# Main_Schematic.net
KiCad netlist of a schematic drawn in Altium Designer
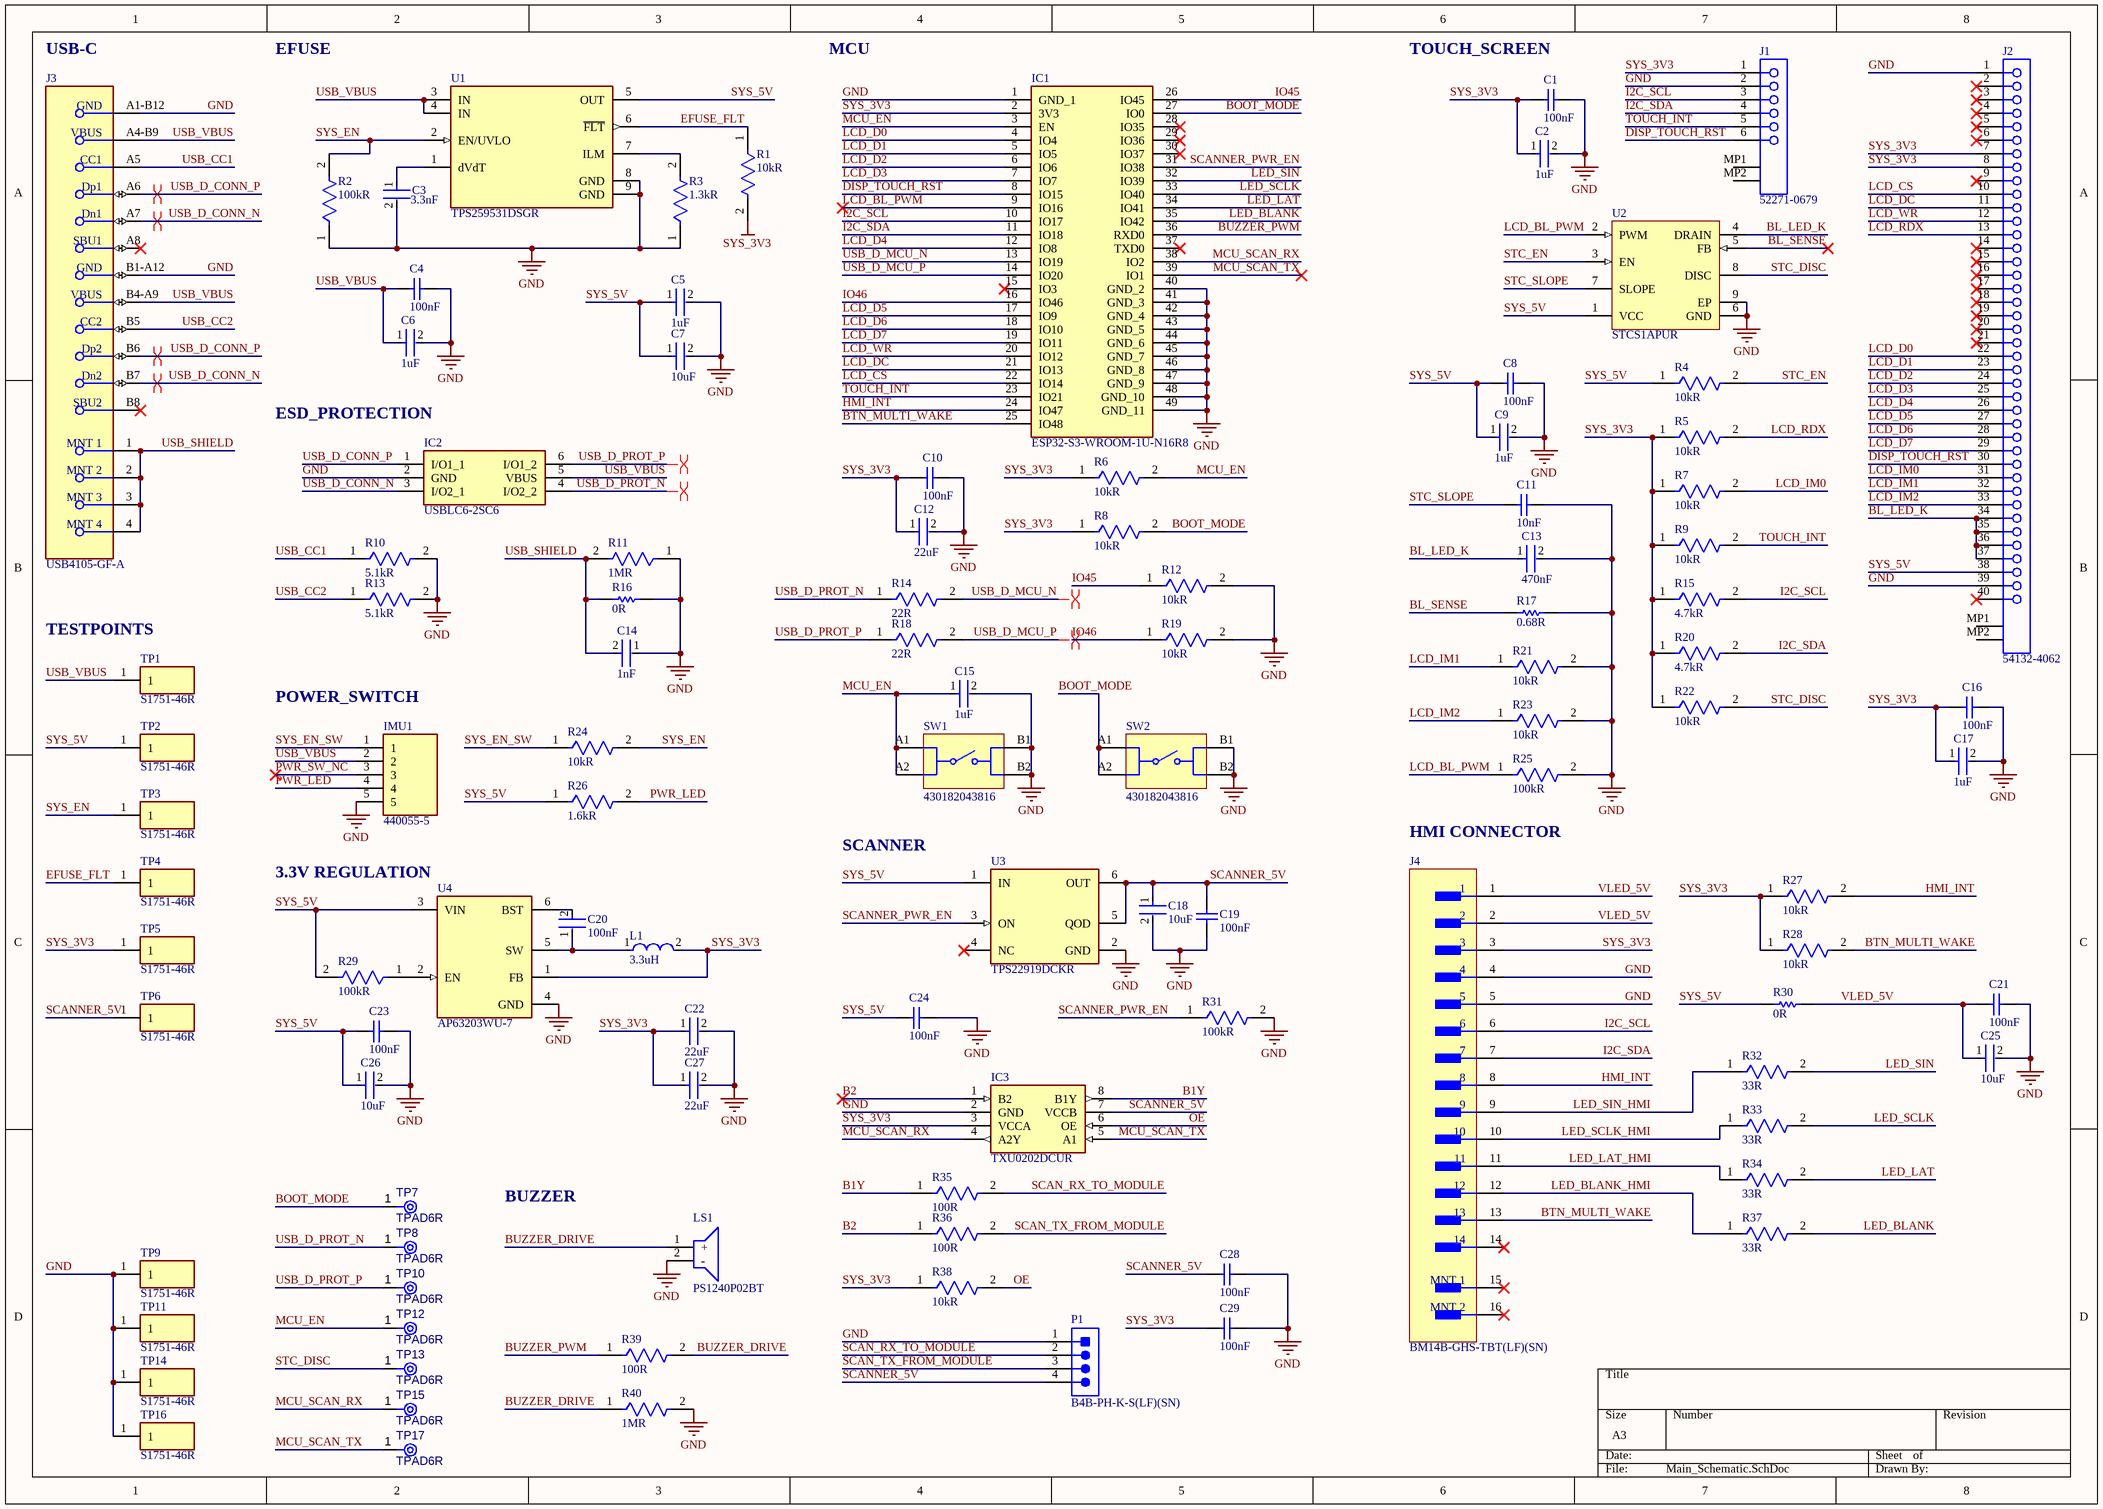
[diagram p0: Main_Schematic.SchDoc]

(export (version "E")
  (design (tool "Eeschema 10.0.6"))
  (components
    (comp (ref "C1")
      (value "100nF")
      (footprint "CAPC1608X90X35ML10T15")
      (description "Chip Capacitor, 100 nF, +/- 10%, 50 V, -55 to 125 degC, 0603 (1608 Metric), RoHS, Tape and Reel")
      (fields (field (name "MANUFACTURER") "Murata"))
      (libsource (lib "Altium Content Vault") (part "CAP-NP-2"))
    )
    (comp (ref "C2")
      (value "1uF")
      (footprint "FP-GRT188-0_1-e0_2_0_5-IPC_C")
      (description "Multi-Layer Ceramic Capacitor 1uF 25V X7R ±10% 0603 Paper T/R")
      (libsource (lib "Altium Content Vault") (part "02cd4be3c70576c341d710602a673aa"))
    )
    (comp (ref "C3")
      (value "3.3nF")
      (footprint "FP-GCM188-0_1-IPC_A")
      (description "Ceramic Capacitor for Automotive 3.3nF  ±5% 50VDC C0G 0603 Paper T/R")
      (fields (field (name "TOLERANCE") "5%"))
      (libsource (lib "Altium Content Vault") (part "02cd4be3c70576c341d710602a673aa"))
    )
    (comp (ref "C4")
      (value "100nF")
      (footprint "CAPC1608X90X35ML10T15")
      (description "Chip Capacitor, 100 nF, +/- 10%, 50 V, -55 to 125 degC, 0603 (1608 Metric), RoHS, Tape and Reel")
      (fields (field (name "MANUFACTURER") "Murata"))
      (libsource (lib "Altium Content Vault") (part "CAP-NP-2"))
    )
    (comp (ref "C5")
      (value "1uF")
      (footprint "FP-GRT188-0_1-e0_2_0_5-IPC_C")
      (description "Multi-Layer Ceramic Capacitor 1uF 25V X7R ±10% 0603 Paper T/R")
      (libsource (lib "Altium Content Vault") (part "02cd4be3c70576c341d710602a673aa"))
    )
    (comp (ref "C6")
      (value "1uF")
      (footprint "FP-GRT188-0_1-e0_2_0_5-IPC_C")
      (description "Multi-Layer Ceramic Capacitor 1uF 25V X7R ±10% 0603 Paper T/R")
      (libsource (lib "Altium Content Vault") (part "02cd4be3c70576c341d710602a673aa"))
    )
    (comp (ref "C7")
      (value "10uF")
      (footprint "FP-GRM21B-0_15-IPC_A")
      (description "Chip Multilayer Ceramic Capacitors for General Purpose, 0805, 10uF, X5R, 15%, 20%, 25V")
      (fields (field (name "TOLERANCE") "20%"))
      (libsource (lib "Altium Content Vault") (part "b4654b650e69147ec39a6b967a45e02"))
    )
    (comp (ref "C8")
      (value "100nF")
      (footprint "CAPC1608X90X35ML10T15")
      (description "Chip Capacitor, 100 nF, +/- 10%, 50 V, -55 to 125 degC, 0603 (1608 Metric), RoHS, Tape and Reel")
      (fields (field (name "MANUFACTURER") "Murata"))
      (libsource (lib "Altium Content Vault") (part "CAP-NP-2"))
    )
    (comp (ref "C9")
      (value "1uF")
      (footprint "FP-GRT188-0_1-e0_2_0_5-IPC_C")
      (description "Multi-Layer Ceramic Capacitor 1uF 25V X7R ±10% 0603 Paper T/R")
      (libsource (lib "Altium Content Vault") (part "02cd4be3c70576c341d710602a673aa"))
    )
    (comp (ref "C10")
      (value "100nF")
      (footprint "CAPC1608X90X35ML10T15")
      (description "Chip Capacitor, 100 nF, +/- 10%, 50 V, -55 to 125 degC, 0603 (1608 Metric), RoHS, Tape and Reel")
      (fields (field (name "MANUFACTURER") "Murata"))
      (libsource (lib "Altium Content Vault") (part "CAP-NP-2"))
    )
    (comp (ref "C11")
      (value "10nF")
      (footprint "CAPC1608X87X35LL15T15")
      (fields (field (name "MANUFACTURER") "Kemet") (field (name "PART NUMBER") "C0603C103J5RALTU"))
      (libsource (lib "Altium Content Vault") (part "CAP"))
    )
    (comp (ref "C12")
      (value "22uF")
      (footprint "FP-GRM319-0_15-IPC_C")
      (description "Chip Multilayer Ceramic Capacitors for General Purpose, 1206, 22uF, X5R, 15%, 20%, 16V")
      (fields (field (name "TOLERANCE") "20%"))
      (libsource (lib "Altium Content Vault") (part "b4654b650e69147ec39a6b967a45e02"))
    )
    (comp (ref "C13")
      (value "470nF")
      (footprint "FP-C0603C-CF-MFG")
      (description "CAP CER SMD 0603 .47UF 5% X7R 16")
      (fields (field (name "TOLERANCE") "0.05") (field (name "MANUFACTURER") "KEMET"))
      (libsource (lib "Altium Content Vault") (part "b4654b650e69147ec39a6b967a45e02"))
    )
    (comp (ref "C14")
      (value "1nF")
      (footprint "FP-GCJ188-0_2-IPC_A")
      (description "Cap Ceramic 1000pF 50V X7R 10% Pad SMD 0603 Soft Termination +125°C Automotive T/R")
      (fields (field (name "TOLERANCE") "10%"))
      (libsource (lib "Altium Content Vault") (part "f23184f103b6ebe33a8c269c53dcba6"))
    )
    (comp (ref "C15")
      (value "1uF")
      (footprint "FP-GRT188-0_1-e0_2_0_5-IPC_C")
      (description "Multi-Layer Ceramic Capacitor 1uF 25V X7R ±10% 0603 Paper T/R")
      (libsource (lib "Altium Content Vault") (part "02cd4be3c70576c341d710602a673aa"))
    )
    (comp (ref "C16")
      (value "100nF")
      (footprint "CAPC1608X90X35ML10T15")
      (description "Chip Capacitor, 100 nF, +/- 10%, 50 V, -55 to 125 degC, 0603 (1608 Metric), RoHS, Tape and Reel")
      (fields (field (name "MANUFACTURER") "Murata"))
      (libsource (lib "Altium Content Vault") (part "CAP-NP-2"))
    )
    (comp (ref "C17")
      (value "1uF")
      (footprint "FP-GRT188-0_1-e0_2_0_5-IPC_C")
      (description "Multi-Layer Ceramic Capacitor 1uF 25V X7R ±10% 0603 Paper T/R")
      (libsource (lib "Altium Content Vault") (part "02cd4be3c70576c341d710602a673aa"))
    )
    (comp (ref "C18")
      (value "10uF")
      (footprint "FP-GRM21B-0_15-IPC_A")
      (description "Chip Multilayer Ceramic Capacitors for General Purpose, 0805, 10uF, X5R, 15%, 20%, 25V")
      (fields (field (name "TOLERANCE") "20%"))
      (libsource (lib "Altium Content Vault") (part "b4654b650e69147ec39a6b967a45e02"))
    )
    (comp (ref "C19")
      (value "100nF")
      (footprint "CAPC1608X90X35ML10T15")
      (description "Chip Capacitor, 100 nF, +/- 10%, 50 V, -55 to 125 degC, 0603 (1608 Metric), RoHS, Tape and Reel")
      (fields (field (name "MANUFACTURER") "Murata"))
      (libsource (lib "Altium Content Vault") (part "CAP-NP-2"))
    )
    (comp (ref "C20")
      (value "100nF")
      (footprint "FP-GCJ188-0_2-IPC_C")
      (description "Cap Ceramic 0.1uF 50V X7R 10% Pad SMD 0603 Soft Termination +125°C Automotive T/R")
      (fields (field (name "TOLERANCE") "10%"))
      (libsource (lib "Altium Content Vault") (part "f23184f103b6ebe33a8c269c53dcba6"))
    )
    (comp (ref "C21")
      (value "100nF")
      (footprint "CAPC1608X90X35ML10T15")
      (description "Chip Capacitor, 100 nF, +/- 10%, 50 V, -55 to 125 degC, 0603 (1608 Metric), RoHS, Tape and Reel")
      (fields (field (name "MANUFACTURER") "Murata"))
      (libsource (lib "Altium Content Vault") (part "CAP-NP-2"))
    )
    (comp (ref "C22")
      (value "22uF")
      (footprint "FP-GRM319-0_15-IPC_C")
      (description "Chip Multilayer Ceramic Capacitors for General Purpose, 1206, 22uF, X5R, 15%, 20%, 16V")
      (fields (field (name "TOLERANCE") "20%"))
      (libsource (lib "Altium Content Vault") (part "b4654b650e69147ec39a6b967a45e02"))
    )
    (comp (ref "C23")
      (value "100nF")
      (footprint "CAPC1608X90X35ML10T15")
      (description "Chip Capacitor, 100 nF, +/- 10%, 50 V, -55 to 125 degC, 0603 (1608 Metric), RoHS, Tape and Reel")
      (fields (field (name "MANUFACTURER") "Murata"))
      (libsource (lib "Altium Content Vault") (part "CAP-NP-2"))
    )
    (comp (ref "C24")
      (value "100nF")
      (footprint "CAPC1608X90X35ML10T15")
      (description "Chip Capacitor, 100 nF, +/- 10%, 50 V, -55 to 125 degC, 0603 (1608 Metric), RoHS, Tape and Reel")
      (fields (field (name "MANUFACTURER") "Murata"))
      (libsource (lib "Altium Content Vault") (part "CAP-NP-2"))
    )
    (comp (ref "C25")
      (value "10uF")
      (footprint "FP-GRM21B-0_15-IPC_A")
      (description "Chip Multilayer Ceramic Capacitors for General Purpose, 0805, 10uF, X5R, 15%, 20%, 25V")
      (fields (field (name "TOLERANCE") "20%"))
      (libsource (lib "Altium Content Vault") (part "b4654b650e69147ec39a6b967a45e02"))
    )
    (comp (ref "C26")
      (value "10uF")
      (footprint "FP-GRM21B-0_15-IPC_A")
      (description "Chip Multilayer Ceramic Capacitors for General Purpose, 0805, 10uF, X5R, 15%, 20%, 25V")
      (fields (field (name "TOLERANCE") "20%"))
      (libsource (lib "Altium Content Vault") (part "b4654b650e69147ec39a6b967a45e02"))
    )
    (comp (ref "C27")
      (value "22uF")
      (footprint "FP-GRM319-0_15-IPC_C")
      (description "Chip Multilayer Ceramic Capacitors for General Purpose, 1206, 22uF, X5R, 15%, 20%, 16V")
      (fields (field (name "TOLERANCE") "20%"))
      (libsource (lib "Altium Content Vault") (part "b4654b650e69147ec39a6b967a45e02"))
    )
    (comp (ref "C28")
      (value "100nF")
      (footprint "CAPC1608X90X35ML10T15")
      (description "Chip Capacitor, 100 nF, +/- 10%, 50 V, -55 to 125 degC, 0603 (1608 Metric), RoHS, Tape and Reel")
      (fields (field (name "MANUFACTURER") "Murata"))
      (libsource (lib "Altium Content Vault") (part "CAP-NP-2"))
    )
    (comp (ref "C29")
      (value "100nF")
      (footprint "CAPC1608X90X35ML10T15")
      (description "Chip Capacitor, 100 nF, +/- 10%, 50 V, -55 to 125 degC, 0603 (1608 Metric), RoHS, Tape and Reel")
      (fields (field (name "MANUFACTURER") "Murata"))
      (libsource (lib "Altium Content Vault") (part "CAP-NP-2"))
    )
    (comp (ref "IC1")
      (value "ESP32-S3-WROOM-1U-N16R8")
      (footprint "SamacSys:ESP32S3WROOM1UN16R8")
      (description "Integrated Circuit")
      (fields (field (name "MOUSER PART NUMBER") "356-ESP32S3WM1UN16R8"))
      (libsource (lib "*") (part "ESP32-S3-WROOM-1U-N16R8"))
    )
    (comp (ref "IC2")
      (value "USBLC6-2SC6")
      (footprint "SamacSys:SOT95P280X145-6N")
      (description "Integrated Circuit")
      (fields (field (name "MOUSER PART NUMBER") "511-USBLC6-2SC6"))
      (libsource (lib "SamacSys") (part "USBLC6-2SC6"))
    )
    (comp (ref "IC3")
      (value "TXU0202DCUR")
      (footprint "SamacSys:SOP50P310X90-8N")
      (description "Integrated Circuit")
      (fields (field (name "MOUSER PART NUMBER") "595-TXU0202DCUR"))
      (libsource (lib "*") (part "TXU0202DCUR"))
    )
    (comp (ref "IMU1")
      (value "440055-5")
      (footprint "SamacSys:4400555")
      (description "Connector")
      (fields (field (name "MOUSER PART NUMBER") "571-440055-5"))
      (libsource (lib "*") (part "440055-5"))
    )
    (comp (ref "J1")
      (value "52271-0679")
      (footprint "MOLX-52271-0679")
      (fields (field (name "MANUFACTURER") "Molex"))
      (libsource (lib "Altium Content Vault") (part "MOLX-52271-0679"))
    )
    (comp (ref "J2")
      (value "54132-4062")
      (footprint "MOLX-54132-4062")
      (fields (field (name "MANUFACTURER") "Molex"))
      (libsource (lib "Altium Content Vault") (part "MOLX-54132-4062"))
    )
    (comp (ref "J3")
      (value "USB4105-GF-A")
      (footprint "FP-USB4105-GF-A-MFG")
      (description "CONN RCPT USB2.0 TYPEC 5A")
      (fields
        (field (name "MANUFACTURER") "GCT")
        (field (name "OCTOPART") "https://octopart.com/usb4105-gf-a-gct-106627878")
      )
      (libsource (lib "Altium Content Vault") (part "e7c17a616881a82b79941196b4bec10"))
    )
    (comp (ref "J4")
      (value "BM14B-GHS-TBT(LF)(SN)")
      (footprint "FP-BM14B-GHS-TBT_LF_SN-MFG")
      (description "BM14B-GHS-TBT(LF)(SN) Conn Shrouded Header HDR 14 POS 1.25mm Solder ST Top Entry SMD T/R")
      (libsource (lib "Altium Content Vault") (part "4e16b2d45535132dfc94a0c32fbd9e7"))
    )
    (comp (ref "L1")
      (value "3.3uH")
      (footprint "FP-SRP4020TA-MFG")
      (description "FIXED IND 3.3UH 3.5A 76 MOHM SMD")
      (fields
        (field (name "OCTOPART") "https://octopart.com/srp4020ta-3r3m-bourns-47300338")
        (field (name "MANUFACTURER") "Bourns")
      )
      (libsource (lib "Altium Content Vault") (part "725321dda6339637d4d059423bc1c3c"))
    )
    (comp (ref "LS1")
      (value "PS1240P02BT")
      (footprint "SamacSys:PS1240P02BT")
      (description "Loudspeaker or Buzzer")
      (fields (field (name "MOUSER PART NUMBER") "810-PS1240P02BT"))
      (libsource (lib "*") (part "PS1240P02BT"))
    )
    (comp (ref "P1")
      (value "B4B-PH-K-S(LF)(SN)")
      (footprint "JST-B4B-PH-K-S_V")
      (fields (field (name "MANUFACTURER") "JST"))
      (libsource (lib "Altium Content Vault") (part "CN-1P-M-R4"))
    )
    (comp (ref "R1")
      (value "10kR")
      (footprint "FP-AC0603-IPC_A")
      (description "RES 10kΩ 5.00% 0.2W 0603")
      (libsource (lib "Altium Content Vault") (part "1029c3af85768c4190bb7ad29bc67b5"))
    )
    (comp (ref "R2")
      (value "100kR")
      (footprint "FP-AC0603-IPC_A")
      (description "RES 100kΩ 1.00% 0.2W 0603")
      (libsource (lib "Altium Content Vault") (part "1029c3af85768c4190bb7ad29bc67b5"))
    )
    (comp (ref "R3")
      (value "1.3kR")
      (footprint "FP-RMCF0603-MFG")
      (description "1.3kΩ ±5% 0.1W 0603 Thick Film Chip Resistor AEC-Q200 compliant")
      (fields (field (name "TOLERANCE") "5%"))
      (libsource (lib "Altium Content Vault") (part "1029c3af85768c4190bb7ad29bc67b5"))
    )
    (comp (ref "R4")
      (value "10kR")
      (footprint "FP-AC0603-IPC_A")
      (description "RES 10kΩ 5.00% 0.2W 0603")
      (libsource (lib "Altium Content Vault") (part "1029c3af85768c4190bb7ad29bc67b5"))
    )
    (comp (ref "R5")
      (value "10kR")
      (footprint "FP-AC0603-IPC_A")
      (description "RES 10kΩ 5.00% 0.2W 0603")
      (libsource (lib "Altium Content Vault") (part "1029c3af85768c4190bb7ad29bc67b5"))
    )
    (comp (ref "R6")
      (value "10kR")
      (footprint "FP-AC0603-IPC_A")
      (description "RES 10kΩ 5.00% 0.2W 0603")
      (libsource (lib "Altium Content Vault") (part "1029c3af85768c4190bb7ad29bc67b5"))
    )
    (comp (ref "R7")
      (value "10kR")
      (footprint "FP-AC0603-IPC_A")
      (description "RES 10kΩ 5.00% 0.2W 0603")
      (libsource (lib "Altium Content Vault") (part "1029c3af85768c4190bb7ad29bc67b5"))
    )
    (comp (ref "R8")
      (value "10kR")
      (footprint "FP-AC0603-IPC_A")
      (description "RES 10kΩ 5.00% 0.2W 0603")
      (libsource (lib "Altium Content Vault") (part "1029c3af85768c4190bb7ad29bc67b5"))
    )
    (comp (ref "R9")
      (value "10kR")
      (footprint "FP-AC0603-IPC_A")
      (description "RES 10kΩ 5.00% 0.2W 0603")
      (libsource (lib "Altium Content Vault") (part "1029c3af85768c4190bb7ad29bc67b5"))
    )
    (comp (ref "R10")
      (value "5.1kR")
      (footprint "FP-AT0603-IPC_B")
      (description "Thin Film Chip Resistors Automotive Grade 5.1kΩ 1% 50ppm/°C 0603")
      (libsource (lib "Altium Content Vault") (part "1029c3af85768c4190bb7ad29bc67b5"))
    )
    (comp (ref "R11")
      (value "1MR")
      (footprint "FP-RMCF0805-IPC_C")
      (description "1MΩ ±5% 0.125W 0805 Thick Film Chip Resistor AEC-Q200 compliant")
      (fields (field (name "TOLERANCE") "5%"))
      (libsource (lib "Altium Content Vault") (part "1029c3af85768c4190bb7ad29bc67b5"))
    )
    (comp (ref "R12")
      (value "10kR")
      (footprint "FP-AC0603-IPC_A")
      (description "RES 10kΩ 5.00% 0.2W 0603")
      (libsource (lib "Altium Content Vault") (part "1029c3af85768c4190bb7ad29bc67b5"))
    )
    (comp (ref "R13")
      (value "5.1kR")
      (footprint "FP-AT0603-IPC_B")
      (description "Thin Film Chip Resistors Automotive Grade 5.1kΩ 1% 50ppm/°C 0603")
      (libsource (lib "Altium Content Vault") (part "1029c3af85768c4190bb7ad29bc67b5"))
    )
    (comp (ref "R14")
      (value "22R")
      (footprint "FP-RMCF0603-IPC_A")
      (description "22Ω ±5% 0.1W 0603 Thick Film Chip Resistor AEC-Q200 compliant")
      (fields (field (name "TOLERANCE") "5%"))
      (libsource (lib "Altium Content Vault") (part "1029c3af85768c4190bb7ad29bc67b5"))
    )
    (comp (ref "R15")
      (value "4.7kR")
      (footprint "FP-RN732A-MFG")
      (description "SMD Chip Resistor, Thin Film, 4.7KΩ, 100 V, 0805 [2012 Metric], 100 mW, 0.1%, RN73 Series")
      (fields (field (name "TOLERANCE") "0.1%") (field (name "MANUFACTURER") "TE Connectivity"))
      (libsource (lib "Altium Content Vault") (part "1029c3af85768c4190bb7ad29bc67b5"))
    )
    (comp (ref "R16")
      (value "0R")
      (footprint "RESC2013X60X35ML10T20")
      (fields (field (name "TOLERANCE") "5%") (field (name "MANUFACTURER") "Yageo"))
      (libsource (lib "Altium Content Vault") (part "RES-2"))
    )
    (comp (ref "R17")
      (value "0.68R")
      (footprint "RESC1608X55X30NL15T15")
      (fields (field (name "PART NUMBER") "ERJ-3RQFR68V") (field (name "MANUFACTURER") "Panasonic"))
      (libsource (lib "Altium Content Vault") (part "RES"))
    )
    (comp (ref "R18")
      (value "22R")
      (footprint "FP-RMCF0603-IPC_A")
      (description "22Ω ±5% 0.1W 0603 Thick Film Chip Resistor AEC-Q200 compliant")
      (fields (field (name "TOLERANCE") "5%"))
      (libsource (lib "Altium Content Vault") (part "1029c3af85768c4190bb7ad29bc67b5"))
    )
    (comp (ref "R19")
      (value "10kR")
      (footprint "FP-AC0603-IPC_A")
      (description "RES 10kΩ 5.00% 0.2W 0603")
      (libsource (lib "Altium Content Vault") (part "1029c3af85768c4190bb7ad29bc67b5"))
    )
    (comp (ref "R20")
      (value "4.7kR")
      (footprint "FP-RN732A-MFG")
      (description "SMD Chip Resistor, Thin Film, 4.7KΩ, 100 V, 0805 [2012 Metric], 100 mW, 0.1%, RN73 Series")
      (fields (field (name "TOLERANCE") "0.1%") (field (name "MANUFACTURER") "TE Connectivity"))
      (libsource (lib "Altium Content Vault") (part "1029c3af85768c4190bb7ad29bc67b5"))
    )
    (comp (ref "R21")
      (value "10kR")
      (footprint "FP-AC0603-IPC_A")
      (description "RES 10kΩ 5.00% 0.2W 0603")
      (libsource (lib "Altium Content Vault") (part "1029c3af85768c4190bb7ad29bc67b5"))
    )
    (comp (ref "R22")
      (value "10kR")
      (footprint "FP-AC0603-IPC_A")
      (description "RES 10kΩ 5.00% 0.2W 0603")
      (libsource (lib "Altium Content Vault") (part "1029c3af85768c4190bb7ad29bc67b5"))
    )
    (comp (ref "R23")
      (value "10kR")
      (footprint "FP-AC0603-IPC_A")
      (description "RES 10kΩ 5.00% 0.2W 0603")
      (libsource (lib "Altium Content Vault") (part "1029c3af85768c4190bb7ad29bc67b5"))
    )
    (comp (ref "R24")
      (value "10kR")
      (footprint "FP-AC0603-IPC_A")
      (description "RES 10kΩ 5.00% 0.2W 0603")
      (libsource (lib "Altium Content Vault") (part "1029c3af85768c4190bb7ad29bc67b5"))
    )
    (comp (ref "R25")
      (value "100kR")
      (footprint "FP-AC0603-IPC_A")
      (description "RES 100kΩ 1.00% 0.2W 0603")
      (libsource (lib "Altium Content Vault") (part "1029c3af85768c4190bb7ad29bc67b5"))
    )
    (comp (ref "R26")
      (value "1.6kR")
      (footprint "FP-RT0603-MFG")
      (description "RES SMD 1.6K OHM 1% 1/10W 0603")
      (fields (field (name "MANUFACTURER PART NUMBER") "RT0603FRE071K6L") (field (name "TOLERANCE") "0.01"))
      (libsource (lib "Altium Content Vault") (part "1029c3af85768c4190bb7ad29bc67b5"))
    )
    (comp (ref "R27")
      (value "10kR")
      (footprint "FP-AC0603-IPC_A")
      (description "RES 10kΩ 5.00% 0.2W 0603")
      (libsource (lib "Altium Content Vault") (part "1029c3af85768c4190bb7ad29bc67b5"))
    )
    (comp (ref "R28")
      (value "10kR")
      (footprint "FP-AC0603-IPC_A")
      (description "RES 10kΩ 5.00% 0.2W 0603")
      (libsource (lib "Altium Content Vault") (part "1029c3af85768c4190bb7ad29bc67b5"))
    )
    (comp (ref "R29")
      (value "100kR")
      (footprint "FP-AC0603-IPC_A")
      (description "RES 100kΩ 1.00% 0.2W 0603")
      (libsource (lib "Altium Content Vault") (part "1029c3af85768c4190bb7ad29bc67b5"))
    )
    (comp (ref "R30")
      (value "0R")
      (footprint "RESC2013X60X35ML10T20")
      (fields (field (name "TOLERANCE") "5%") (field (name "MANUFACTURER") "Yageo"))
      (libsource (lib "Altium Content Vault") (part "RES-2"))
    )
    (comp (ref "R31")
      (value "100kR")
      (footprint "FP-AC0603-IPC_A")
      (description "RES 100kΩ 1.00% 0.2W 0603")
      (libsource (lib "Altium Content Vault") (part "1029c3af85768c4190bb7ad29bc67b5"))
    )
    (comp (ref "R32")
      (value "33R")
      (footprint "FP-RMCF0805-MFG")
      (description "33Ω ±1% 0.125W 0805 Thick Film Chip Resistor AEC-Q200 compliant")
      (fields (field (name "TOLERANCE") "1%"))
      (libsource (lib "Altium Content Vault") (part "1029c3af85768c4190bb7ad29bc67b5"))
    )
    (comp (ref "R33")
      (value "33R")
      (footprint "FP-RMCF0805-MFG")
      (description "33Ω ±1% 0.125W 0805 Thick Film Chip Resistor AEC-Q200 compliant")
      (fields (field (name "TOLERANCE") "1%"))
      (libsource (lib "Altium Content Vault") (part "1029c3af85768c4190bb7ad29bc67b5"))
    )
    (comp (ref "R34")
      (value "33R")
      (footprint "FP-RMCF0805-MFG")
      (description "33Ω ±1% 0.125W 0805 Thick Film Chip Resistor AEC-Q200 compliant")
      (fields (field (name "TOLERANCE") "1%"))
      (libsource (lib "Altium Content Vault") (part "1029c3af85768c4190bb7ad29bc67b5"))
    )
    (comp (ref "R35")
      (value "100R")
      (footprint "FP-RNCP0603-MFG")
      (description "100Ω ±1% 0.125W 0603 High Power Anti-Sulfur Thin Film Chip Resistor")
      (fields (field (name "TOLERANCE") "1%"))
      (libsource (lib "Altium Content Vault") (part "1029c3af85768c4190bb7ad29bc67b5"))
    )
    (comp (ref "R36")
      (value "100R")
      (footprint "FP-RNCP0603-MFG")
      (description "100Ω ±1% 0.125W 0603 High Power Anti-Sulfur Thin Film Chip Resistor")
      (fields (field (name "TOLERANCE") "1%"))
      (libsource (lib "Altium Content Vault") (part "1029c3af85768c4190bb7ad29bc67b5"))
    )
    (comp (ref "R37")
      (value "33R")
      (footprint "FP-RMCF0805-MFG")
      (description "33Ω ±1% 0.125W 0805 Thick Film Chip Resistor AEC-Q200 compliant")
      (fields (field (name "TOLERANCE") "1%"))
      (libsource (lib "Altium Content Vault") (part "1029c3af85768c4190bb7ad29bc67b5"))
    )
    (comp (ref "R38")
      (value "10kR")
      (footprint "FP-AC0603-IPC_A")
      (description "RES 10kΩ 5.00% 0.2W 0603")
      (libsource (lib "Altium Content Vault") (part "1029c3af85768c4190bb7ad29bc67b5"))
    )
    (comp (ref "R39")
      (value "100R")
      (footprint "FP-RNCP0603-MFG")
      (description "100Ω ±1% 0.125W 0603 High Power Anti-Sulfur Thin Film Chip Resistor")
      (fields (field (name "TOLERANCE") "1%"))
      (libsource (lib "Altium Content Vault") (part "1029c3af85768c4190bb7ad29bc67b5"))
    )
    (comp (ref "R40")
      (value "1MR")
      (footprint "FP-RMCF0805-IPC_C")
      (description "1MΩ ±5% 0.125W 0805 Thick Film Chip Resistor AEC-Q200 compliant")
      (fields (field (name "TOLERANCE") "5%"))
      (libsource (lib "Altium Content Vault") (part "1029c3af85768c4190bb7ad29bc67b5"))
    )
    (comp (ref "SW1")
      (value "430182043816")
      (footprint "430182043816")
      (description "Switch Tactile N.O. SPST Round Button Gull Wing 0.05A 12VDC 1000000Cycles 1.57N SMD Reel")
      (libsource (lib "Altium Content Vault") (part "SPST-NO_4P"))
    )
    (comp (ref "SW2")
      (value "430182043816")
      (footprint "430182043816")
      (description "Switch Tactile N.O. SPST Round Button Gull Wing 0.05A 12VDC 1000000Cycles 1.57N SMD Reel")
      (libsource (lib "Altium Content Vault") (part "SPST-NO_4P"))
    )
    (comp (ref "TP1")
      (value "S1751-46R")
      (footprint "SamacSys:S175146R")
      (description "Test Point")
      (fields (field (name "MOUSER PART NUMBER") "855-S1751-46R"))
      (libsource (lib "*") (part "S1751-46R"))
    )
    (comp (ref "TP2")
      (value "S1751-46R")
      (footprint "SamacSys:S175146R")
      (description "Test Point")
      (fields (field (name "MOUSER PART NUMBER") "855-S1751-46R"))
      (libsource (lib "*") (part "S1751-46R"))
    )
    (comp (ref "TP3")
      (value "S1751-46R")
      (footprint "SamacSys:S175146R")
      (description "Test Point")
      (fields (field (name "MOUSER PART NUMBER") "855-S1751-46R"))
      (libsource (lib "*") (part "S1751-46R"))
    )
    (comp (ref "TP4")
      (value "S1751-46R")
      (footprint "SamacSys:S175146R")
      (description "Test Point")
      (fields (field (name "MOUSER PART NUMBER") "855-S1751-46R"))
      (libsource (lib "*") (part "S1751-46R"))
    )
    (comp (ref "TP5")
      (value "S1751-46R")
      (footprint "SamacSys:S175146R")
      (description "Test Point")
      (fields (field (name "MOUSER PART NUMBER") "855-S1751-46R"))
      (libsource (lib "*") (part "S1751-46R"))
    )
    (comp (ref "TP6")
      (value "S1751-46R")
      (footprint "SamacSys:S175146R")
      (description "Test Point")
      (fields (field (name "MOUSER PART NUMBER") "855-S1751-46R"))
      (libsource (lib "*") (part "S1751-46R"))
    )
    (comp (ref "TP7")
      (value "TPAD6R")
      (footprint "TP06R")
      (description "0.6mm round")
      (libsource (lib "Luca Guebeli") (part "CMP-001-0001-4"))
    )
    (comp (ref "TP8")
      (value "TPAD6R")
      (footprint "TP06R")
      (description "0.6mm round")
      (libsource (lib "Luca Guebeli") (part "CMP-001-0001-4"))
    )
    (comp (ref "TP9")
      (value "S1751-46R")
      (footprint "SamacSys:S175146R")
      (description "Test Point")
      (fields (field (name "MOUSER PART NUMBER") "855-S1751-46R"))
      (libsource (lib "*") (part "S1751-46R"))
    )
    (comp (ref "TP10")
      (value "TPAD6R")
      (footprint "TP06R")
      (description "0.6mm round")
      (libsource (lib "Luca Guebeli") (part "CMP-001-0001-4"))
    )
    (comp (ref "TP11")
      (value "S1751-46R")
      (footprint "SamacSys:S175146R")
      (description "Test Point")
      (fields (field (name "MOUSER PART NUMBER") "855-S1751-46R"))
      (libsource (lib "*") (part "S1751-46R"))
    )
    (comp (ref "TP12")
      (value "TPAD6R")
      (footprint "TP06R")
      (description "0.6mm round")
      (libsource (lib "Luca Guebeli") (part "CMP-001-0001-4"))
    )
    (comp (ref "TP13")
      (value "TPAD6R")
      (footprint "TP06R")
      (description "0.6mm round")
      (libsource (lib "Luca Guebeli") (part "CMP-001-0001-4"))
    )
    (comp (ref "TP14")
      (value "S1751-46R")
      (footprint "SamacSys:S175146R")
      (description "Test Point")
      (fields (field (name "MOUSER PART NUMBER") "855-S1751-46R"))
      (libsource (lib "*") (part "S1751-46R"))
    )
    (comp (ref "TP15")
      (value "TPAD6R")
      (footprint "TP06R")
      (description "0.6mm round")
      (libsource (lib "Luca Guebeli") (part "CMP-001-0001-4"))
    )
    (comp (ref "TP16")
      (value "S1751-46R")
      (footprint "SamacSys:S175146R")
      (description "Test Point")
      (fields (field (name "MOUSER PART NUMBER") "855-S1751-46R"))
      (libsource (lib "*") (part "S1751-46R"))
    )
    (comp (ref "TP17")
      (value "TPAD6R")
      (footprint "TP06R")
      (description "0.6mm round")
      (libsource (lib "Luca Guebeli") (part "CMP-001-0001-4"))
    )
    (comp (ref "U1")
      (value "TPS259531DSGR")
      (footprint "FP-DSG0008A-IPC_A")
      (description "IC PWR MGMT EFUSE 2.7-18V 8WSON")
      (libsource (lib "Altium Content Vault") (part "be8a6ed96e7e7970ff670e6b7a0d8cd"))
    )
    (comp (ref "U2")
      (value "STCS1APUR")
      (footprint "DFN8(3x3)-P050_N")
      (description "1.5A Max Constant Current LED driver, 8-Pin VDFPN, Tape and Reel")
      (libsource (lib "Altium Content Vault") (part "PM-REG-STCS1A-IL9"))
    )
    (comp (ref "U3")
      (value "TPS22919DCKR")
      (footprint "FP-DCK0006A-MFG")
      (description "POWER MANAGEMENT")
      (libsource (lib "Altium Content Vault") (part "7dede5ae6ec4f64f362f8612ed9bb45"))
    )
    (comp (ref "U4")
      (value "AP63203WU-7")
      (footprint "FP-TSOT26-MFG")
      (description "IC REG BUCK 3.3V 2A TSOT26")
      (fields
        (field (name "MANUFACTURER") "Diodes Inc.")
        (field (name "OCTOPART") "https://octopart.com/ap63203wu-7-diodes+inc.-98099550")
      )
      (libsource (lib "Altium Content Vault") (part "0e61c2974d7114b43f01ef96ae2e524"))
    )
  )
  (nets
    (net (code "1") (name "/B1Y") (class "Default")
      (node (ref "IC3") (pin "8") (pinfunction "B1Y_8") (pintype "output"))
      (node (ref "R35") (pin "1") (pinfunction "1_1") (pintype "passive"))
    )
    (net (code "2") (name "/B2") (class "Default")
      (node (ref "IC3") (pin "1") (pinfunction "B2_1") (pintype "input"))
      (node (ref "R36") (pin "1") (pinfunction "1_1") (pintype "passive"))
    )
    (net (code "3") (name "/BL_LED_K") (class "Default")
      (node (ref "C13") (pin "1") (pinfunction "1_1") (pintype "passive"))
      (node (ref "J2") (pin "34") (pinfunction "34_34") (pintype "passive"))
      (node (ref "J2") (pin "35") (pinfunction "35_35") (pintype "passive"))
      (node (ref "J2") (pin "36") (pinfunction "36_36") (pintype "passive"))
      (node (ref "J2") (pin "37") (pinfunction "37_37") (pintype "passive"))
      (node (ref "U2") (pin "4") (pinfunction "DRAIN_4") (pintype "open_collector"))
    )
    (net (code "4") (name "/BL_SENSE") (class "Default")
      (node (ref "R17") (pin "1") (pinfunction "1_1") (pintype "passive"))
      (node (ref "U2") (pin "5") (pinfunction "FB_5") (pintype "input"))
    )
    (net (code "5") (name "/BOOT_MODE") (class "Default")
      (node (ref "IC1") (pin "27") (pinfunction "IO0_27") (pintype "passive"))
      (node (ref "R8") (pin "2") (pinfunction "2_2") (pintype "passive"))
      (node (ref "SW2") (pin "A1") (pinfunction "A1_A1") (pintype "passive"))
      (node (ref "SW2") (pin "A2") (pinfunction "A2_A2") (pintype "passive"))
      (node (ref "TP7") (pin "1") (pinfunction "TP_1") (pintype "passive"))
    )
    (net (code "6") (name "/BTN_MULTI_WAKE") (class "Default")
      (node (ref "IC1") (pin "25") (pinfunction "IO48_25") (pintype "passive"))
      (node (ref "J4") (pin "13") (pinfunction "13_13") (pintype "passive"))
      (node (ref "R28") (pin "2") (pinfunction "2_2") (pintype "passive"))
    )
    (net (code "7") (name "/BUZZER_DRIVE") (class "Default")
      (node (ref "LS1") (pin "1") (pinfunction "+_1") (pintype "passive"))
      (node (ref "R39") (pin "2") (pinfunction "2_2") (pintype "passive"))
      (node (ref "R40") (pin "1") (pinfunction "1_1") (pintype "passive"))
    )
    (net (code "8") (name "/BUZZER_PWM") (class "Default")
      (node (ref "IC1") (pin "36") (pinfunction "RXD0_36") (pintype "passive"))
      (node (ref "R39") (pin "1") (pinfunction "1_1") (pintype "passive"))
    )
    (net (code "9") (name "/DISP_TOUCH_RST") (class "Default")
      (node (ref "IC1") (pin "8") (pinfunction "IO15_8") (pintype "passive"))
      (node (ref "J1") (pin "6") (pinfunction "6_6") (pintype "passive"))
      (node (ref "J2") (pin "30") (pinfunction "30_30") (pintype "passive"))
    )
    (net (code "10") (name "/EFUSE_FLT") (class "Default")
      (node (ref "R1") (pin "1") (pinfunction "1_1") (pintype "passive"))
      (node (ref "TP4") (pin "1") (pinfunction "1_1") (pintype "passive"))
      (node (ref "U1") (pin "6") (pinfunction "~{FLT}_6") (pintype "output"))
    )
    (net (code "11") (name "/HMI_INT") (class "Default")
      (node (ref "IC1") (pin "24") (pinfunction "IO47_24") (pintype "passive"))
      (node (ref "J4") (pin "8") (pinfunction "8_8") (pintype "passive"))
      (node (ref "R27") (pin "2") (pinfunction "2_2") (pintype "passive"))
    )
    (net (code "12") (name "/I2C_SCL") (class "Default")
      (node (ref "IC1") (pin "10") (pinfunction "IO17_10") (pintype "passive"))
      (node (ref "J1") (pin "3") (pinfunction "3_3") (pintype "passive"))
      (node (ref "J4") (pin "6") (pinfunction "6_6") (pintype "passive"))
      (node (ref "R15") (pin "2") (pinfunction "2_2") (pintype "passive"))
    )
    (net (code "13") (name "/I2C_SDA") (class "Default")
      (node (ref "IC1") (pin "11") (pinfunction "IO18_11") (pintype "passive"))
      (node (ref "J1") (pin "4") (pinfunction "4_4") (pintype "passive"))
      (node (ref "J4") (pin "7") (pinfunction "7_7") (pintype "passive"))
      (node (ref "R20") (pin "2") (pinfunction "2_2") (pintype "passive"))
    )
    (net (code "14") (name "/IO45") (class "Default")
      (node (ref "IC1") (pin "26") (pinfunction "IO45_26") (pintype "passive"))
      (node (ref "R12") (pin "1") (pinfunction "1_1") (pintype "passive"))
    )
    (net (code "15") (name "/IO46") (class "Default")
      (node (ref "IC1") (pin "16") (pinfunction "IO46_16") (pintype "passive"))
      (node (ref "R19") (pin "1") (pinfunction "1_1") (pintype "passive"))
    )
    (net (code "16") (name "/LCD_BL_PWM") (class "Default")
      (node (ref "IC1") (pin "9") (pinfunction "IO16_9") (pintype "passive"))
      (node (ref "R25") (pin "1") (pinfunction "1_1") (pintype "passive"))
      (node (ref "U2") (pin "2") (pinfunction "PWM_2") (pintype "input"))
    )
    (net (code "17") (name "/LCD_CS") (class "Default")
      (node (ref "IC1") (pin "22") (pinfunction "IO14_22") (pintype "passive"))
      (node (ref "J2") (pin "10") (pinfunction "10_10") (pintype "passive"))
    )
    (net (code "18") (name "/LCD_D0") (class "Default")
      (node (ref "IC1") (pin "4") (pinfunction "IO4_4") (pintype "passive"))
      (node (ref "J2") (pin "22") (pinfunction "22_22") (pintype "passive"))
    )
    (net (code "19") (name "/LCD_D1") (class "Default")
      (node (ref "IC1") (pin "5") (pinfunction "IO5_5") (pintype "passive"))
      (node (ref "J2") (pin "23") (pinfunction "23_23") (pintype "passive"))
    )
    (net (code "20") (name "/LCD_D2") (class "Default")
      (node (ref "IC1") (pin "6") (pinfunction "IO6_6") (pintype "passive"))
      (node (ref "J2") (pin "24") (pinfunction "24_24") (pintype "passive"))
    )
    (net (code "21") (name "/LCD_D3") (class "Default")
      (node (ref "IC1") (pin "7") (pinfunction "IO7_7") (pintype "passive"))
      (node (ref "J2") (pin "25") (pinfunction "25_25") (pintype "passive"))
    )
    (net (code "22") (name "/LCD_D4") (class "Default")
      (node (ref "IC1") (pin "12") (pinfunction "IO8_12") (pintype "passive"))
      (node (ref "J2") (pin "26") (pinfunction "26_26") (pintype "passive"))
    )
    (net (code "23") (name "/LCD_D5") (class "Default")
      (node (ref "IC1") (pin "17") (pinfunction "IO9_17") (pintype "passive"))
      (node (ref "J2") (pin "27") (pinfunction "27_27") (pintype "passive"))
    )
    (net (code "24") (name "/LCD_D6") (class "Default")
      (node (ref "IC1") (pin "18") (pinfunction "IO10_18") (pintype "passive"))
      (node (ref "J2") (pin "28") (pinfunction "28_28") (pintype "passive"))
    )
    (net (code "25") (name "/LCD_D7") (class "Default")
      (node (ref "IC1") (pin "19") (pinfunction "IO11_19") (pintype "passive"))
      (node (ref "J2") (pin "29") (pinfunction "29_29") (pintype "passive"))
    )
    (net (code "26") (name "/LCD_DC") (class "Default")
      (node (ref "IC1") (pin "21") (pinfunction "IO13_21") (pintype "passive"))
      (node (ref "J2") (pin "11") (pinfunction "11_11") (pintype "passive"))
    )
    (net (code "27") (name "/LCD_IM0") (class "Default")
      (node (ref "J2") (pin "31") (pinfunction "31_31") (pintype "passive"))
      (node (ref "R7") (pin "2") (pinfunction "2_2") (pintype "passive"))
    )
    (net (code "28") (name "/LCD_IM1") (class "Default")
      (node (ref "J2") (pin "32") (pinfunction "32_32") (pintype "passive"))
      (node (ref "R21") (pin "1") (pinfunction "1_1") (pintype "passive"))
    )
    (net (code "29") (name "/LCD_IM2") (class "Default")
      (node (ref "J2") (pin "33") (pinfunction "33_33") (pintype "passive"))
      (node (ref "R23") (pin "1") (pinfunction "1_1") (pintype "passive"))
    )
    (net (code "30") (name "/LCD_RDX") (class "Default")
      (node (ref "J2") (pin "13") (pinfunction "13_13") (pintype "passive"))
      (node (ref "R5") (pin "2") (pinfunction "2_2") (pintype "passive"))
    )
    (net (code "31") (name "/LCD_WR") (class "Default")
      (node (ref "IC1") (pin "20") (pinfunction "IO12_20") (pintype "passive"))
      (node (ref "J2") (pin "12") (pinfunction "12_12") (pintype "passive"))
    )
    (net (code "32") (name "/LED_BLANK") (class "Default")
      (node (ref "IC1") (pin "35") (pinfunction "IO42_35") (pintype "passive"))
      (node (ref "R37") (pin "2") (pinfunction "2_2") (pintype "passive"))
    )
    (net (code "33") (name "/LED_BLANK_HMI") (class "Default")
      (node (ref "J4") (pin "12") (pinfunction "12_12") (pintype "passive"))
      (node (ref "R37") (pin "1") (pinfunction "1_1") (pintype "passive"))
    )
    (net (code "34") (name "/LED_LAT") (class "Default")
      (node (ref "IC1") (pin "34") (pinfunction "IO41_34") (pintype "passive"))
      (node (ref "R34") (pin "2") (pinfunction "2_2") (pintype "passive"))
    )
    (net (code "35") (name "/LED_LAT_HMI") (class "Default")
      (node (ref "J4") (pin "11") (pinfunction "11_11") (pintype "passive"))
      (node (ref "R34") (pin "1") (pinfunction "1_1") (pintype "passive"))
    )
    (net (code "36") (name "/LED_SCLK") (class "Default")
      (node (ref "IC1") (pin "33") (pinfunction "IO40_33") (pintype "passive"))
      (node (ref "R33") (pin "2") (pinfunction "2_2") (pintype "passive"))
    )
    (net (code "37") (name "/LED_SCLK_HMI") (class "Default")
      (node (ref "J4") (pin "10") (pinfunction "10_10") (pintype "passive"))
      (node (ref "R33") (pin "1") (pinfunction "1_1") (pintype "passive"))
    )
    (net (code "38") (name "/LED_SIN") (class "Default")
      (node (ref "IC1") (pin "32") (pinfunction "IO39_32") (pintype "passive"))
      (node (ref "R32") (pin "2") (pinfunction "2_2") (pintype "passive"))
    )
    (net (code "39") (name "/LED_SIN_HMI") (class "Default")
      (node (ref "J4") (pin "9") (pinfunction "9_9") (pintype "passive"))
      (node (ref "R32") (pin "1") (pinfunction "1_1") (pintype "passive"))
    )
    (net (code "40") (name "/MCU_EN") (class "Default")
      (node (ref "C15") (pin "1") (pinfunction "1_1") (pintype "passive"))
      (node (ref "IC1") (pin "3") (pinfunction "EN_3") (pintype "passive"))
      (node (ref "R6") (pin "2") (pinfunction "2_2") (pintype "passive"))
      (node (ref "SW1") (pin "A1") (pinfunction "A1_A1") (pintype "passive"))
      (node (ref "SW1") (pin "A2") (pinfunction "A2_A2") (pintype "passive"))
      (node (ref "TP12") (pin "1") (pinfunction "TP_1") (pintype "passive"))
    )
    (net (code "41") (name "/MCU_SCAN_RX") (class "Default")
      (node (ref "IC1") (pin "38") (pinfunction "IO2_38") (pintype "passive"))
      (node (ref "IC3") (pin "4") (pinfunction "A2Y_4") (pintype "output"))
      (node (ref "TP15") (pin "1") (pinfunction "TP_1") (pintype "passive"))
    )
    (net (code "42") (name "/MCU_SCAN_TX") (class "Default")
      (node (ref "IC1") (pin "39") (pinfunction "IO1_39") (pintype "passive"))
      (node (ref "IC3") (pin "5") (pinfunction "A1_5") (pintype "input"))
      (node (ref "TP17") (pin "1") (pinfunction "TP_1") (pintype "passive"))
    )
    (net (code "43") (name "/OE") (class "Default")
      (node (ref "IC3") (pin "6") (pinfunction "OE_6") (pintype "input"))
      (node (ref "R38") (pin "2") (pinfunction "2_2") (pintype "passive"))
    )
    (net (code "44") (name "/PWR_LED") (class "Default")
      (node (ref "IMU1") (pin "4") (pinfunction "4_4") (pintype "passive"))
      (node (ref "R26") (pin "2") (pinfunction "2_2") (pintype "passive"))
    )
    (net (code "45") (name "/PWR_SW_NC") (class "Default")
      (node (ref "IMU1") (pin "3") (pinfunction "3_3") (pintype "passive+no_connect"))
    )
    (net (code "46") (name "/SCANNER_5V") (class "Default")
      (node (ref "C18") (pin "1") (pinfunction "1_1") (pintype "passive"))
      (node (ref "C19") (pin "2") (pinfunction "2_2") (pintype "passive"))
      (node (ref "C28") (pin "2") (pinfunction "2_2") (pintype "passive"))
      (node (ref "IC3") (pin "7") (pinfunction "VCCB_7") (pintype "power_in"))
      (node (ref "P1") (pin "4") (pinfunction "4_4") (pintype "passive"))
      (node (ref "TP6") (pin "1") (pinfunction "1_1") (pintype "passive"))
      (node (ref "U3") (pin "5") (pinfunction "QOD_5") (pintype "passive"))
      (node (ref "U3") (pin "6") (pinfunction "OUT_6") (pintype "power_in"))
    )
    (net (code "47") (name "/SCANNER_PWR_EN") (class "Default")
      (node (ref "IC1") (pin "31") (pinfunction "IO38_31") (pintype "passive"))
      (node (ref "R31") (pin "1") (pinfunction "1_1") (pintype "passive"))
      (node (ref "U3") (pin "3") (pinfunction "ON_3") (pintype "input"))
    )
    (net (code "48") (name "/SCAN_RX_TO_MODULE") (class "Default")
      (node (ref "P1") (pin "2") (pinfunction "2_2") (pintype "passive"))
      (node (ref "R35") (pin "2") (pinfunction "2_2") (pintype "passive"))
    )
    (net (code "49") (name "/SCAN_TX_FROM_MODULE") (class "Default")
      (node (ref "P1") (pin "3") (pinfunction "3_3") (pintype "passive"))
      (node (ref "R36") (pin "2") (pinfunction "2_2") (pintype "passive"))
    )
    (net (code "50") (name "/STC_DISC") (class "Default")
      (node (ref "R22") (pin "2") (pinfunction "2_2") (pintype "passive"))
      (node (ref "TP13") (pin "1") (pinfunction "TP_1") (pintype "passive"))
      (node (ref "U2") (pin "8") (pinfunction "DISC_8") (pintype "open_collector"))
    )
    (net (code "51") (name "/STC_EN") (class "Default")
      (node (ref "R4") (pin "2") (pinfunction "2_2") (pintype "passive"))
      (node (ref "U2") (pin "3") (pinfunction "EN_3") (pintype "input"))
    )
    (net (code "52") (name "/STC_SLOPE") (class "Default")
      (node (ref "C11") (pin "1") (pinfunction "1_1") (pintype "passive"))
      (node (ref "U2") (pin "7") (pinfunction "SLOPE_7") (pintype "passive"))
    )
    (net (code "53") (name "/SYS_5V") (class "Default")
      (node (ref "C23") (pin "2") (pinfunction "2_2") (pintype "passive"))
      (node (ref "C24") (pin "2") (pinfunction "2_2") (pintype "passive"))
      (node (ref "C26") (pin "1") (pinfunction "1_1") (pintype "passive"))
      (node (ref "C5") (pin "1") (pinfunction "1_1") (pintype "passive"))
      (node (ref "C7") (pin "1") (pinfunction "1_1") (pintype "passive"))
      (node (ref "C8") (pin "2") (pinfunction "2_2") (pintype "passive"))
      (node (ref "C9") (pin "1") (pinfunction "1_1") (pintype "passive"))
      (node (ref "J2") (pin "38") (pinfunction "38_38") (pintype "passive"))
      (node (ref "R26") (pin "1") (pinfunction "1_1") (pintype "passive"))
      (node (ref "R29") (pin "2") (pinfunction "2_2") (pintype "passive"))
      (node (ref "R30") (pin "1") (pinfunction "1_1") (pintype "passive"))
      (node (ref "R4") (pin "1") (pinfunction "1_1") (pintype "passive"))
      (node (ref "TP2") (pin "1") (pinfunction "1_1") (pintype "passive"))
      (node (ref "U1") (pin "5") (pinfunction "OUT_5") (pintype "passive"))
      (node (ref "U2") (pin "1") (pinfunction "VCC_1") (pintype "power_in"))
      (node (ref "U3") (pin "1") (pinfunction "IN_1") (pintype "power_in"))
      (node (ref "U4") (pin "3") (pinfunction "VIN_3") (pintype "power_in"))
    )
    (net (code "54") (name "/SYS_EN") (class "Default")
      (node (ref "R2") (pin "2") (pinfunction "2_2") (pintype "passive"))
      (node (ref "R24") (pin "2") (pinfunction "2_2") (pintype "passive"))
      (node (ref "TP3") (pin "1") (pinfunction "1_1") (pintype "passive"))
      (node (ref "U1") (pin "2") (pinfunction "EN/UVLO_2") (pintype "input"))
    )
    (net (code "55") (name "/SYS_EN_SW") (class "Default")
      (node (ref "IMU1") (pin "1") (pinfunction "1_1") (pintype "passive"))
      (node (ref "R24") (pin "1") (pinfunction "1_1") (pintype "passive"))
    )
    (net (code "56") (name "/TOUCH_INT") (class "Default")
      (node (ref "IC1") (pin "23") (pinfunction "IO21_23") (pintype "passive"))
      (node (ref "J1") (pin "5") (pinfunction "5_5") (pintype "passive"))
      (node (ref "R9") (pin "2") (pinfunction "2_2") (pintype "passive"))
    )
    (net (code "57") (name "/USB_CC1") (class "Default")
      (node (ref "J3") (pin "A5") (pinfunction "CC1_A5") (pintype "power_in"))
      (node (ref "R10") (pin "1") (pinfunction "1_1") (pintype "passive"))
    )
    (net (code "58") (name "/USB_CC2") (class "Default")
      (node (ref "J3") (pin "B5") (pinfunction "CC2_B5") (pintype "bidirectional"))
      (node (ref "R13") (pin "1") (pinfunction "1_1") (pintype "passive"))
    )
    (net (code "59") (name "/USB_D_CONN_N") (class "Default")
      (node (ref "IC2") (pin "3") (pinfunction "I/O2_1_3") (pintype "passive"))
      (node (ref "J3") (pin "A7") (pinfunction "Dn1_A7") (pintype "bidirectional"))
      (node (ref "J3") (pin "B7") (pinfunction "Dn2_B7") (pintype "bidirectional"))
    )
    (net (code "60") (name "/USB_D_CONN_P") (class "Default")
      (node (ref "IC2") (pin "1") (pinfunction "I/O1_1_1") (pintype "passive"))
      (node (ref "J3") (pin "A6") (pinfunction "Dp1_A6") (pintype "bidirectional"))
      (node (ref "J3") (pin "B6") (pinfunction "Dp2_B6") (pintype "bidirectional"))
    )
    (net (code "61") (name "/USB_D_MCU_N") (class "Default")
      (node (ref "IC1") (pin "13") (pinfunction "IO19_13") (pintype "passive"))
      (node (ref "R14") (pin "2") (pinfunction "2_2") (pintype "passive"))
    )
    (net (code "62") (name "/USB_D_MCU_P") (class "Default")
      (node (ref "IC1") (pin "14") (pinfunction "IO20_14") (pintype "passive"))
      (node (ref "R18") (pin "2") (pinfunction "2_2") (pintype "passive"))
    )
    (net (code "63") (name "/USB_D_PROT_N") (class "Default")
      (node (ref "IC2") (pin "4") (pinfunction "I/O2_2_4") (pintype "passive"))
      (node (ref "R14") (pin "1") (pinfunction "1_1") (pintype "passive"))
      (node (ref "TP8") (pin "1") (pinfunction "TP_1") (pintype "passive"))
    )
    (net (code "64") (name "/USB_D_PROT_P") (class "Default")
      (node (ref "IC2") (pin "6") (pinfunction "I/O1_2_6") (pintype "passive"))
      (node (ref "R18") (pin "1") (pinfunction "1_1") (pintype "passive"))
      (node (ref "TP10") (pin "1") (pinfunction "TP_1") (pintype "passive"))
    )
    (net (code "65") (name "/USB_SHIELD") (class "Default")
      (node (ref "C14") (pin "2") (pinfunction "2_2") (pintype "passive"))
      (node (ref "J3") (pin "1") (pinfunction "MNT_1_1") (pintype "power_in"))
      (node (ref "J3") (pin "2") (pinfunction "MNT_2_2") (pintype "power_in"))
      (node (ref "J3") (pin "3") (pinfunction "MNT_3_3") (pintype "power_in"))
      (node (ref "J3") (pin "4") (pinfunction "MNT_4_4") (pintype "power_in"))
      (node (ref "R11") (pin "2") (pinfunction "2_2") (pintype "passive"))
      (node (ref "R16") (pin "1") (pinfunction "1_1") (pintype "passive"))
    )
    (net (code "66") (name "/USB_VBUS") (class "Default")
      (node (ref "C4") (pin "2") (pinfunction "2_2") (pintype "passive"))
      (node (ref "C6") (pin "1") (pinfunction "1_1") (pintype "passive"))
      (node (ref "IC2") (pin "5") (pinfunction "VBUS_5") (pintype "passive"))
      (node (ref "IMU1") (pin "2") (pinfunction "2_2") (pintype "passive"))
      (node (ref "J3") (pin "A4-B9") (pinfunction "VBUS_A4-B9") (pintype "power_in"))
      (node (ref "J3") (pin "B4-A9") (pinfunction "VBUS_B4-A9") (pintype "bidirectional"))
      (node (ref "TP1") (pin "1") (pinfunction "1_1") (pintype "passive"))
      (node (ref "U1") (pin "3") (pinfunction "IN_3") (pintype "power_in"))
      (node (ref "U1") (pin "4") (pinfunction "IN_4") (pintype "power_in"))
    )
    (net (code "67") (name "/VLED_5V") (class "Default")
      (node (ref "C21") (pin "2") (pinfunction "2_2") (pintype "passive"))
      (node (ref "C25") (pin "1") (pinfunction "1_1") (pintype "passive"))
      (node (ref "J4") (pin "1") (pinfunction "1_1") (pintype "passive"))
      (node (ref "J4") (pin "2") (pinfunction "2_2") (pintype "passive"))
      (node (ref "R30") (pin "2") (pinfunction "2_2") (pintype "passive"))
    )
    (net (code "68") (name "GND") (class "Default")
      (node (ref "C1") (pin "1") (pinfunction "1_1") (pintype "passive"))
      (node (ref "C10") (pin "1") (pinfunction "1_1") (pintype "passive"))
      (node (ref "C11") (pin "2") (pinfunction "2_2") (pintype "passive"))
      (node (ref "C12") (pin "2") (pinfunction "2_2") (pintype "passive"))
      (node (ref "C13") (pin "2") (pinfunction "2_2") (pintype "passive"))
      (node (ref "C14") (pin "1") (pinfunction "1_1") (pintype "passive"))
      (node (ref "C15") (pin "2") (pinfunction "2_2") (pintype "passive"))
      (node (ref "C16") (pin "1") (pinfunction "1_1") (pintype "passive"))
      (node (ref "C17") (pin "2") (pinfunction "2_2") (pintype "passive"))
      (node (ref "C18") (pin "2") (pinfunction "2_2") (pintype "passive"))
      (node (ref "C19") (pin "1") (pinfunction "1_1") (pintype "passive"))
      (node (ref "C2") (pin "2") (pinfunction "2_2") (pintype "passive"))
      (node (ref "C21") (pin "1") (pinfunction "1_1") (pintype "passive"))
      (node (ref "C22") (pin "2") (pinfunction "2_2") (pintype "passive"))
      (node (ref "C23") (pin "1") (pinfunction "1_1") (pintype "passive"))
      (node (ref "C24") (pin "1") (pinfunction "1_1") (pintype "passive"))
      (node (ref "C25") (pin "2") (pinfunction "2_2") (pintype "passive"))
      (node (ref "C26") (pin "2") (pinfunction "2_2") (pintype "passive"))
      (node (ref "C27") (pin "2") (pinfunction "2_2") (pintype "passive"))
      (node (ref "C28") (pin "1") (pinfunction "1_1") (pintype "passive"))
      (node (ref "C29") (pin "1") (pinfunction "1_1") (pintype "passive"))
      (node (ref "C3") (pin "2") (pinfunction "2_2") (pintype "passive"))
      (node (ref "C4") (pin "1") (pinfunction "1_1") (pintype "passive"))
      (node (ref "C5") (pin "2") (pinfunction "2_2") (pintype "passive"))
      (node (ref "C6") (pin "2") (pinfunction "2_2") (pintype "passive"))
      (node (ref "C7") (pin "2") (pinfunction "2_2") (pintype "passive"))
      (node (ref "C8") (pin "1") (pinfunction "1_1") (pintype "passive"))
      (node (ref "C9") (pin "2") (pinfunction "2_2") (pintype "passive"))
      (node (ref "IC1") (pin "1") (pinfunction "GND_1_1") (pintype "passive"))
      (node (ref "IC1") (pin "40") (pinfunction "GND_2_40") (pintype "passive"))
      (node (ref "IC1") (pin "41") (pinfunction "GND_3_41") (pintype "passive"))
      (node (ref "IC1") (pin "42") (pinfunction "GND_4_42") (pintype "passive"))
      (node (ref "IC1") (pin "43") (pinfunction "GND_5_43") (pintype "passive"))
      (node (ref "IC1") (pin "44") (pinfunction "GND_6_44") (pintype "passive"))
      (node (ref "IC1") (pin "45") (pinfunction "GND_7_45") (pintype "passive"))
      (node (ref "IC1") (pin "46") (pinfunction "GND_8_46") (pintype "passive"))
      (node (ref "IC1") (pin "47") (pinfunction "GND_9_47") (pintype "passive"))
      (node (ref "IC1") (pin "48") (pinfunction "GND_10_48") (pintype "passive"))
      (node (ref "IC1") (pin "49") (pinfunction "GND_11_49") (pintype "passive"))
      (node (ref "IC2") (pin "2") (pinfunction "GND_2") (pintype "passive"))
      (node (ref "IC3") (pin "2") (pinfunction "GND_2") (pintype "power_in"))
      (node (ref "IMU1") (pin "5") (pinfunction "5_5") (pintype "passive"))
      (node (ref "J1") (pin "2") (pinfunction "2_2") (pintype "passive"))
      (node (ref "J2") (pin "1") (pinfunction "1_1") (pintype "passive"))
      (node (ref "J2") (pin "39") (pinfunction "39_39") (pintype "passive"))
      (node (ref "J3") (pin "A1-B12") (pinfunction "GND_A1-B12") (pintype "power_in"))
      (node (ref "J3") (pin "B1-A12") (pinfunction "GND_B1-A12") (pintype "bidirectional"))
      (node (ref "J4") (pin "4") (pinfunction "4_4") (pintype "passive"))
      (node (ref "J4") (pin "5") (pinfunction "5_5") (pintype "passive"))
      (node (ref "LS1") (pin "2") (pinfunction "-_2") (pintype "passive"))
      (node (ref "P1") (pin "1") (pinfunction "1_1") (pintype "passive"))
      (node (ref "R10") (pin "2") (pinfunction "2_2") (pintype "passive"))
      (node (ref "R11") (pin "1") (pinfunction "1_1") (pintype "passive"))
      (node (ref "R12") (pin "2") (pinfunction "2_2") (pintype "passive"))
      (node (ref "R13") (pin "2") (pinfunction "2_2") (pintype "passive"))
      (node (ref "R16") (pin "2") (pinfunction "2_2") (pintype "passive"))
      (node (ref "R17") (pin "2") (pinfunction "2_2") (pintype "passive"))
      (node (ref "R19") (pin "2") (pinfunction "2_2") (pintype "passive"))
      (node (ref "R2") (pin "1") (pinfunction "1_1") (pintype "passive"))
      (node (ref "R21") (pin "2") (pinfunction "2_2") (pintype "passive"))
      (node (ref "R23") (pin "2") (pinfunction "2_2") (pintype "passive"))
      (node (ref "R25") (pin "2") (pinfunction "2_2") (pintype "passive"))
      (node (ref "R3") (pin "1") (pinfunction "1_1") (pintype "passive"))
      (node (ref "R31") (pin "2") (pinfunction "2_2") (pintype "passive"))
      (node (ref "R40") (pin "2") (pinfunction "2_2") (pintype "passive"))
      (node (ref "SW1") (pin "B1") (pinfunction "B1_B1") (pintype "passive"))
      (node (ref "SW1") (pin "B2") (pinfunction "B2_B2") (pintype "passive"))
      (node (ref "SW2") (pin "B1") (pinfunction "B1_B1") (pintype "passive"))
      (node (ref "SW2") (pin "B2") (pinfunction "B2_B2") (pintype "passive"))
      (node (ref "TP11") (pin "1") (pinfunction "1_1") (pintype "passive"))
      (node (ref "TP14") (pin "1") (pinfunction "1_1") (pintype "passive"))
      (node (ref "TP16") (pin "1") (pinfunction "1_1") (pintype "passive"))
      (node (ref "TP9") (pin "1") (pinfunction "1_1") (pintype "passive"))
      (node (ref "U1") (pin "8") (pinfunction "GND_8") (pintype "power_in"))
      (node (ref "U1") (pin "9") (pinfunction "GND_9") (pintype "power_in"))
      (node (ref "U2") (pin "6") (pinfunction "GND_6") (pintype "power_in"))
      (node (ref "U2") (pin "9") (pinfunction "EP_9") (pintype "power_in"))
      (node (ref "U3") (pin "2") (pinfunction "GND_2") (pintype "power_in"))
      (node (ref "U4") (pin "4") (pinfunction "GND_4") (pintype "power_in"))
    )
    (net (code "69") (name "Net-(U1-ILM)") (class "Default")
      (node (ref "R3") (pin "2") (pinfunction "2_2") (pintype "passive"))
      (node (ref "U1") (pin "7") (pinfunction "ILM_7") (pintype "passive"))
    )
    (net (code "70") (name "Net-(U1-dVdT)") (class "Default")
      (node (ref "C3") (pin "1") (pinfunction "1_1") (pintype "passive"))
      (node (ref "U1") (pin "1") (pinfunction "dVdT_1") (pintype "passive"))
    )
    (net (code "71") (name "Net-(U4-BST)") (class "Default")
      (node (ref "C20") (pin "2") (pinfunction "2_2") (pintype "passive"))
      (node (ref "U4") (pin "6") (pinfunction "BST_6") (pintype "passive"))
    )
    (net (code "72") (name "Net-(U4-EN)") (class "Default")
      (node (ref "R29") (pin "1") (pinfunction "1_1") (pintype "passive"))
      (node (ref "U4") (pin "2") (pinfunction "EN_2") (pintype "input"))
    )
    (net (code "73") (name "Net-(U4-SW)") (class "Default")
      (node (ref "C20") (pin "1") (pinfunction "1_1") (pintype "passive"))
      (node (ref "L1") (pin "1") (pinfunction "1_1") (pintype "passive"))
      (node (ref "U4") (pin "5") (pinfunction "SW_5") (pintype "passive"))
    )
    (net (code "74") (name "SYS_3V3") (class "Default")
      (node (ref "C1") (pin "2") (pinfunction "2_2") (pintype "passive"))
      (node (ref "C10") (pin "2") (pinfunction "2_2") (pintype "passive"))
      (node (ref "C12") (pin "1") (pinfunction "1_1") (pintype "passive"))
      (node (ref "C16") (pin "2") (pinfunction "2_2") (pintype "passive"))
      (node (ref "C17") (pin "1") (pinfunction "1_1") (pintype "passive"))
      (node (ref "C2") (pin "1") (pinfunction "1_1") (pintype "passive"))
      (node (ref "C22") (pin "1") (pinfunction "1_1") (pintype "passive"))
      (node (ref "C27") (pin "1") (pinfunction "1_1") (pintype "passive"))
      (node (ref "C29") (pin "2") (pinfunction "2_2") (pintype "passive"))
      (node (ref "IC1") (pin "2") (pinfunction "3V3_2") (pintype "passive"))
      (node (ref "IC3") (pin "3") (pinfunction "VCCA_3") (pintype "power_in"))
      (node (ref "J1") (pin "1") (pinfunction "1_1") (pintype "passive"))
      (node (ref "J2") (pin "7") (pinfunction "7_7") (pintype "passive"))
      (node (ref "J2") (pin "8") (pinfunction "8_8") (pintype "passive"))
      (node (ref "J4") (pin "3") (pinfunction "3_3") (pintype "passive"))
      (node (ref "L1") (pin "2") (pinfunction "2_2") (pintype "passive"))
      (node (ref "R1") (pin "2") (pinfunction "2_2") (pintype "passive"))
      (node (ref "R15") (pin "1") (pinfunction "1_1") (pintype "passive"))
      (node (ref "R20") (pin "1") (pinfunction "1_1") (pintype "passive"))
      (node (ref "R22") (pin "1") (pinfunction "1_1") (pintype "passive"))
      (node (ref "R27") (pin "1") (pinfunction "1_1") (pintype "passive"))
      (node (ref "R28") (pin "1") (pinfunction "1_1") (pintype "passive"))
      (node (ref "R38") (pin "1") (pinfunction "1_1") (pintype "passive"))
      (node (ref "R5") (pin "1") (pinfunction "1_1") (pintype "passive"))
      (node (ref "R6") (pin "1") (pinfunction "1_1") (pintype "passive"))
      (node (ref "R7") (pin "1") (pinfunction "1_1") (pintype "passive"))
      (node (ref "R8") (pin "1") (pinfunction "1_1") (pintype "passive"))
      (node (ref "R9") (pin "1") (pinfunction "1_1") (pintype "passive"))
      (node (ref "TP5") (pin "1") (pinfunction "1_1") (pintype "passive"))
      (node (ref "U4") (pin "1") (pinfunction "FB_1") (pintype "passive"))
    )
    (net (code "75") (name "unconnected-(IC1-IO3-Pad15)") (class "Default")
      (node (ref "IC1") (pin "15") (pinfunction "IO3_15") (pintype "passive+no_connect"))
    )
    (net (code "76") (name "unconnected-(IC1-IO35-Pad28)") (class "Default")
      (node (ref "IC1") (pin "28") (pinfunction "IO35_28") (pintype "passive+no_connect"))
    )
    (net (code "77") (name "unconnected-(IC1-IO36-Pad29)") (class "Default")
      (node (ref "IC1") (pin "29") (pinfunction "IO36_29") (pintype "passive+no_connect"))
    )
    (net (code "78") (name "unconnected-(IC1-IO37-Pad30)") (class "Default")
      (node (ref "IC1") (pin "30") (pinfunction "IO37_30") (pintype "passive+no_connect"))
    )
    (net (code "79") (name "unconnected-(IC1-TXD0-Pad37)") (class "Default")
      (node (ref "IC1") (pin "37") (pinfunction "TXD0_37") (pintype "passive+no_connect"))
    )
    (net (code "80") (name "unconnected-(J1-PadMP1)") (class "Default")
      (node (ref "J1") (pin "MP1") (pinfunction "MP1_MP1") (pintype "passive"))
    )
    (net (code "81") (name "unconnected-(J1-PadMP2)") (class "Default")
      (node (ref "J1") (pin "MP2") (pinfunction "MP2_MP2") (pintype "passive"))
    )
    (net (code "82") (name "unconnected-(J2-Pad2)") (class "Default")
      (node (ref "J2") (pin "2") (pinfunction "2_2") (pintype "passive+no_connect"))
    )
    (net (code "83") (name "unconnected-(J2-Pad3)") (class "Default")
      (node (ref "J2") (pin "3") (pinfunction "3_3") (pintype "passive+no_connect"))
    )
    (net (code "84") (name "unconnected-(J2-Pad4)") (class "Default")
      (node (ref "J2") (pin "4") (pinfunction "4_4") (pintype "passive+no_connect"))
    )
    (net (code "85") (name "unconnected-(J2-Pad5)") (class "Default")
      (node (ref "J2") (pin "5") (pinfunction "5_5") (pintype "passive+no_connect"))
    )
    (net (code "86") (name "unconnected-(J2-Pad6)") (class "Default")
      (node (ref "J2") (pin "6") (pinfunction "6_6") (pintype "passive+no_connect"))
    )
    (net (code "87") (name "unconnected-(J2-Pad9)") (class "Default")
      (node (ref "J2") (pin "9") (pinfunction "9_9") (pintype "passive+no_connect"))
    )
    (net (code "88") (name "unconnected-(J2-Pad14)") (class "Default")
      (node (ref "J2") (pin "14") (pinfunction "14_14") (pintype "passive+no_connect"))
    )
    (net (code "89") (name "unconnected-(J2-Pad15)") (class "Default")
      (node (ref "J2") (pin "15") (pinfunction "15_15") (pintype "passive+no_connect"))
    )
    (net (code "90") (name "unconnected-(J2-Pad16)") (class "Default")
      (node (ref "J2") (pin "16") (pinfunction "16_16") (pintype "passive+no_connect"))
    )
    (net (code "91") (name "unconnected-(J2-Pad17)") (class "Default")
      (node (ref "J2") (pin "17") (pinfunction "17_17") (pintype "passive+no_connect"))
    )
    (net (code "92") (name "unconnected-(J2-Pad18)") (class "Default")
      (node (ref "J2") (pin "18") (pinfunction "18_18") (pintype "passive+no_connect"))
    )
    (net (code "93") (name "unconnected-(J2-Pad19)") (class "Default")
      (node (ref "J2") (pin "19") (pinfunction "19_19") (pintype "passive+no_connect"))
    )
    (net (code "94") (name "unconnected-(J2-Pad20)") (class "Default")
      (node (ref "J2") (pin "20") (pinfunction "20_20") (pintype "passive+no_connect"))
    )
    (net (code "95") (name "unconnected-(J2-Pad21)") (class "Default")
      (node (ref "J2") (pin "21") (pinfunction "21_21") (pintype "passive+no_connect"))
    )
    (net (code "96") (name "unconnected-(J2-Pad40)") (class "Default")
      (node (ref "J2") (pin "40") (pinfunction "40_40") (pintype "passive+no_connect"))
    )
    (net (code "97") (name "unconnected-(J2-PadMP1)") (class "Default")
      (node (ref "J2") (pin "MP1") (pinfunction "MP1_MP1") (pintype "passive"))
    )
    (net (code "98") (name "unconnected-(J2-PadMP2)") (class "Default")
      (node (ref "J2") (pin "MP2") (pinfunction "MP2_MP2") (pintype "passive"))
    )
    (net (code "99") (name "unconnected-(J3-SBU1-PadA8)") (class "Default")
      (node (ref "J3") (pin "A8") (pinfunction "SBU1_A8") (pintype "bidirectional+no_connect"))
    )
    (net (code "100") (name "unconnected-(J3-SBU2-PadB8)") (class "Default")
      (node (ref "J3") (pin "B8") (pinfunction "SBU2_B8") (pintype "power_in+no_connect"))
    )
    (net (code "101") (name "unconnected-(J4-MNT_1-Pad15)") (class "Default")
      (node (ref "J4") (pin "15") (pinfunction "MNT_1_15") (pintype "passive+no_connect"))
    )
    (net (code "102") (name "unconnected-(J4-MNT_2-Pad16)") (class "Default")
      (node (ref "J4") (pin "16") (pinfunction "MNT_2_16") (pintype "passive+no_connect"))
    )
    (net (code "103") (name "unconnected-(J4-Pad14)") (class "Default")
      (node (ref "J4") (pin "14") (pinfunction "14_14") (pintype "passive+no_connect"))
    )
    (net (code "104") (name "unconnected-(U3-NC-Pad4)") (class "Default")
      (node (ref "U3") (pin "4") (pinfunction "NC_4") (pintype "passive+no_connect"))
    )
  )
)
